# FuelGuage.net
KiCad netlist of a schematic drawn in Altium Designer
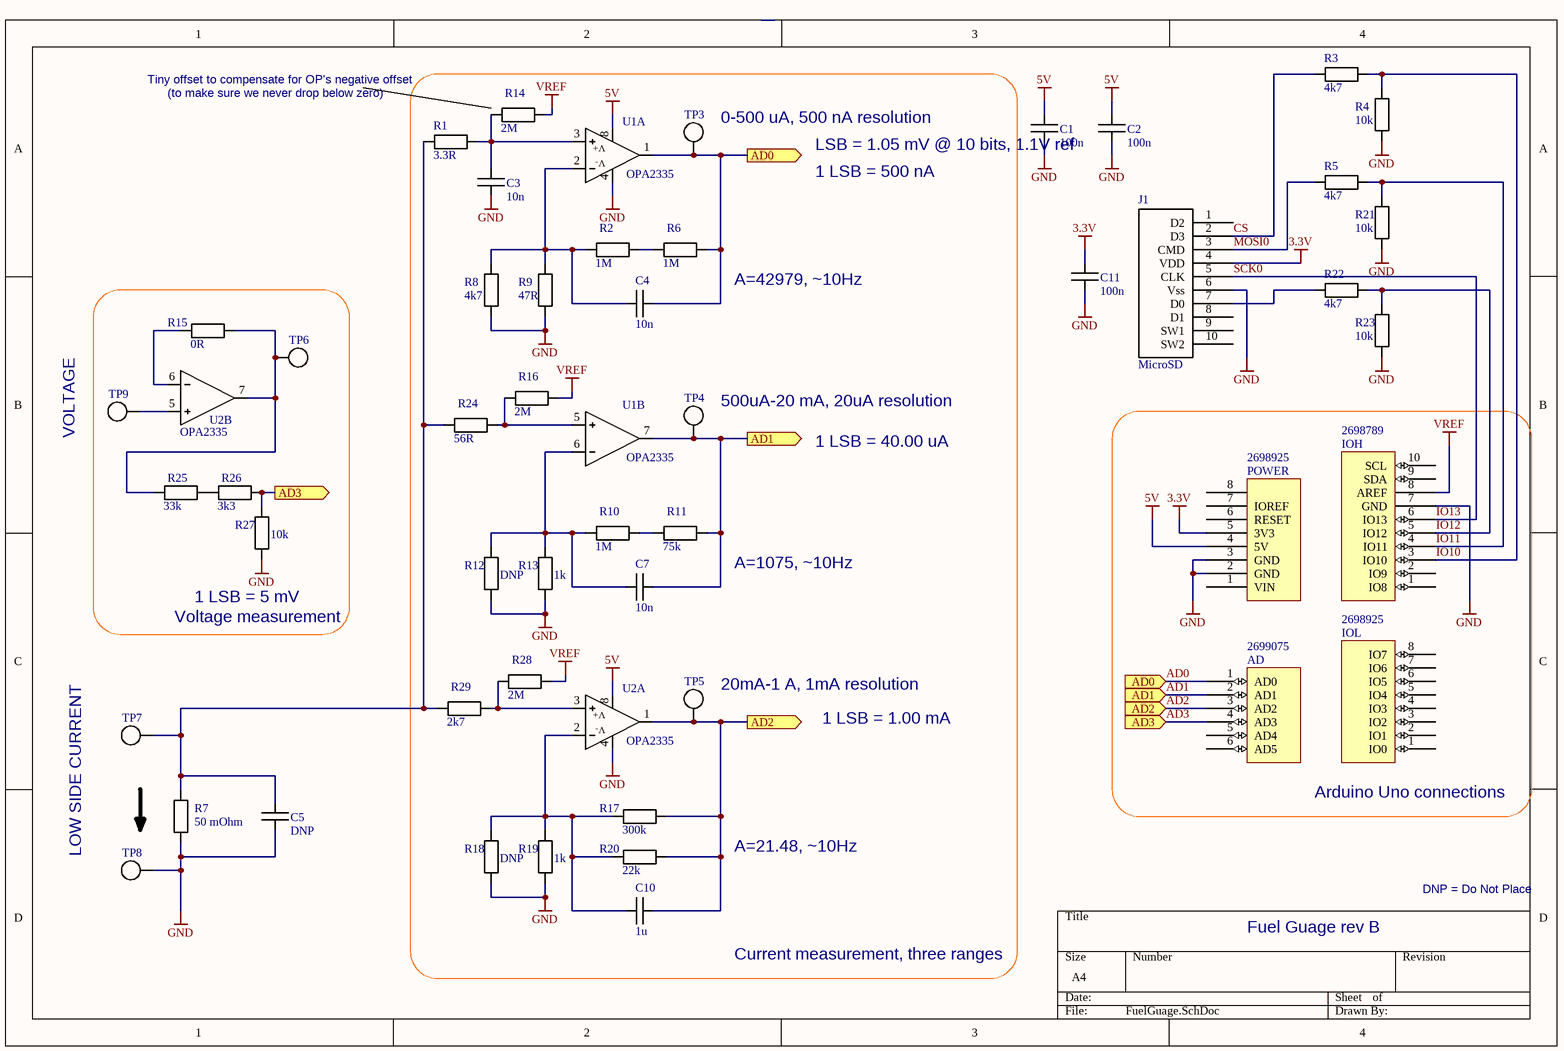
[diagram p0: FuelGuage.SchDoc]

(export (version "E")
  (design (tool "Eeschema 10.0.6"))
  (components
    (comp (ref "AD")
      (value "AD")
      (footprint "Header:Header 6x1 8.5mm")
      (fields (field (name "SUPPLIER PART NUMBER 4") "2699075"))
      (libsource (lib "Header") (part "AD"))
    )
    (comp (ref "C1")
      (value "100n")
      (footprint "0603CAP")
      (description "Ceramic Capacitor SMD 0603")
      (fields (field (name "Comment") "CAP0603"))
      (libsource (lib "PARTS") (part "185"))
    )
    (comp (ref "C2")
      (value "100n")
      (footprint "0603CAP")
      (description "Ceramic Capacitor SMD 0603")
      (fields (field (name "Comment") "CAP0603"))
      (libsource (lib "PARTS") (part "185"))
    )
    (comp (ref "C3")
      (value "10n")
      (footprint "0603CAP")
      (description "Ceramic Capacitor SMD 0603")
      (fields (field (name "Comment") "CAP0603"))
      (libsource (lib "PARTS") (part "185"))
    )
    (comp (ref "C4")
      (value "10n")
      (footprint "0603CAP")
      (description "Ceramic Capacitor SMD 0603")
      (fields (field (name "Comment") "CAP0603"))
      (libsource (lib "PARTS") (part "185"))
    )
    (comp (ref "C5")
      (value "DNP")
      (footprint "0603CAP")
      (description "Ceramic Capacitor SMD 0603")
      (fields (field (name "Comment") "CAP0603"))
      (libsource (lib "PARTS") (part "185"))
    )
    (comp (ref "C7")
      (value "10n")
      (footprint "0603CAP")
      (description "Ceramic Capacitor SMD 0603")
      (fields (field (name "Comment") "CAP0603"))
      (libsource (lib "PARTS") (part "185"))
    )
    (comp (ref "C10")
      (value "1u")
      (footprint "0603CAP")
      (description "Ceramic Capacitor SMD 0603")
      (fields (field (name "Comment") "CAP0603"))
      (libsource (lib "PARTS") (part "185"))
    )
    (comp (ref "C11")
      (value "100n")
      (footprint "0603CAP")
      (description "Ceramic Capacitor SMD 0603")
      (fields (field (name "Comment") "CAP0603"))
      (libsource (lib "PARTS") (part "185"))
    )
    (comp (ref "IOH")
      (value "IOH")
      (footprint "Header:Header 10x1 8.5mm")
      (fields (field (name "SUPPLIER PART NUMBER 3") "2698789"))
      (libsource (lib "Header") (part "IOH"))
    )
    (comp (ref "IOL")
      (value "IOL")
      (footprint "Header 8x1 8.5mm")
      (fields (field (name "SUPPLIER PART NUMBER 4") "2698925"))
      (libsource (lib "Header") (part "IOL"))
    )
    (comp (ref "J1") (value "MicroSD") (footprint "micro SD") (libsource (lib "moja") (part "MicroSD")))
    (comp (ref "POWER")
      (value "POWER_UNO")
      (footprint "Header 8x1 8.5mm")
      (fields (field (name "SUPPLIER PART NUMBER 4") "2698925"))
      (libsource (lib "Header") (part "POWER_UNO"))
    )
    (comp (ref "R1")
      (value "3.3R")
      (footprint "RES0603")
      (description "Resistor 0603 SMD")
      (fields (field (name "Comment") "RES_STANDARD"))
      (libsource (lib "PARTS") (part "276"))
    )
    (comp (ref "R2")
      (value "1M")
      (footprint "RES0603")
      (description "Resistor 0603 SMD")
      (fields (field (name "Comment") "RES_STANDARD"))
      (libsource (lib "PARTS") (part "276"))
    )
    (comp (ref "R3")
      (value "4k7")
      (footprint "RES0603")
      (description "Resistor 0603 SMD")
      (fields (field (name "Comment") "RES_STANDARD"))
      (libsource (lib "PARTS") (part "276"))
    )
    (comp (ref "R4")
      (value "10k")
      (footprint "RES0603")
      (description "Resistor 0603 SMD")
      (fields (field (name "Comment") "RES_STANDARD"))
      (libsource (lib "PARTS") (part "276"))
    )
    (comp (ref "R5")
      (value "4k7")
      (footprint "RES0603")
      (description "Resistor 0603 SMD")
      (fields (field (name "Comment") "RES_STANDARD"))
      (libsource (lib "PARTS") (part "276"))
    )
    (comp (ref "R6")
      (value "1M")
      (footprint "RES0603")
      (description "Resistor 0603 SMD")
      (fields (field (name "Comment") "RES_STANDARD"))
      (libsource (lib "PARTS") (part "276"))
    )
    (comp (ref "R7")
      (value "50 mOhm")
      (footprint "RES0603")
      (description "Resistor 0603 SMD")
      (fields (field (name "Comment") "RES_STANDARD"))
      (libsource (lib "PARTS") (part "276"))
    )
    (comp (ref "R8")
      (value "4k7")
      (footprint "RES0603")
      (description "Resistor 0603 SMD")
      (fields (field (name "Comment") "RES_STANDARD"))
      (libsource (lib "PARTS") (part "276"))
    )
    (comp (ref "R9")
      (value "47R")
      (footprint "RES0603")
      (description "Resistor 0603 SMD")
      (fields (field (name "Comment") "RES_STANDARD"))
      (libsource (lib "PARTS") (part "276"))
    )
    (comp (ref "R10")
      (value "1M")
      (footprint "RES0603")
      (description "Resistor 0603 SMD")
      (fields (field (name "Comment") "RES_STANDARD"))
      (libsource (lib "PARTS") (part "276"))
    )
    (comp (ref "R11")
      (value "75k")
      (footprint "RES0603")
      (description "Resistor 0603 SMD")
      (fields (field (name "Comment") "RES_STANDARD"))
      (libsource (lib "PARTS") (part "276"))
    )
    (comp (ref "R12")
      (value "DNP")
      (footprint "RES0603")
      (description "Resistor 0603 SMD")
      (fields (field (name "Comment") "RES_STANDARD"))
      (libsource (lib "PARTS") (part "276"))
    )
    (comp (ref "R13")
      (value "1k")
      (footprint "RES0603")
      (description "Resistor 0603 SMD")
      (fields (field (name "Comment") "RES_STANDARD"))
      (libsource (lib "PARTS") (part "276"))
    )
    (comp (ref "R14")
      (value "2M")
      (footprint "RES0603")
      (description "Resistor 0603 SMD")
      (fields (field (name "Comment") "RES_STANDARD"))
      (libsource (lib "PARTS") (part "276"))
    )
    (comp (ref "R15")
      (value "0R")
      (footprint "RES0603")
      (description "Resistor 0603 SMD")
      (fields (field (name "Comment") "RES_STANDARD"))
      (libsource (lib "PARTS") (part "276"))
    )
    (comp (ref "R16")
      (value "2M")
      (footprint "RES0603")
      (description "Resistor 0603 SMD")
      (fields (field (name "Comment") "RES_STANDARD"))
      (libsource (lib "PARTS") (part "276"))
    )
    (comp (ref "R17")
      (value "300k")
      (footprint "RES0603")
      (description "Resistor 0603 SMD")
      (fields (field (name "Comment") "RES_STANDARD"))
      (libsource (lib "PARTS") (part "276"))
    )
    (comp (ref "R18")
      (value "DNP")
      (footprint "RES0603")
      (description "Resistor 0603 SMD")
      (fields (field (name "Comment") "RES_STANDARD"))
      (libsource (lib "PARTS") (part "276"))
    )
    (comp (ref "R19")
      (value "1k")
      (footprint "RES0603")
      (description "Resistor 0603 SMD")
      (fields (field (name "Comment") "RES_STANDARD"))
      (libsource (lib "PARTS") (part "276"))
    )
    (comp (ref "R20")
      (value "22k")
      (footprint "RES0603")
      (description "Resistor 0603 SMD")
      (fields (field (name "Comment") "RES_STANDARD"))
      (libsource (lib "PARTS") (part "276"))
    )
    (comp (ref "R21")
      (value "10k")
      (footprint "RES0603")
      (description "Resistor 0603 SMD")
      (fields (field (name "Comment") "RES_STANDARD"))
      (libsource (lib "PARTS") (part "276"))
    )
    (comp (ref "R22")
      (value "4k7")
      (footprint "RES0603")
      (description "Resistor 0603 SMD")
      (fields (field (name "Comment") "RES_STANDARD"))
      (libsource (lib "PARTS") (part "276"))
    )
    (comp (ref "R23")
      (value "10k")
      (footprint "RES0603")
      (description "Resistor 0603 SMD")
      (fields (field (name "Comment") "RES_STANDARD"))
      (libsource (lib "PARTS") (part "276"))
    )
    (comp (ref "R24")
      (value "56R")
      (footprint "RES0603")
      (description "Resistor 0603 SMD")
      (fields (field (name "Comment") "RES_STANDARD"))
      (libsource (lib "PARTS") (part "276"))
    )
    (comp (ref "R25")
      (value "33k")
      (footprint "RES0603")
      (description "Resistor 0603 SMD")
      (fields (field (name "Comment") "RES_STANDARD"))
      (libsource (lib "PARTS") (part "276"))
    )
    (comp (ref "R26")
      (value "3k3")
      (footprint "RES0603")
      (description "Resistor 0603 SMD")
      (fields (field (name "Comment") "RES_STANDARD"))
      (libsource (lib "PARTS") (part "276"))
    )
    (comp (ref "R27")
      (value "10k")
      (footprint "RES0603")
      (description "Resistor 0603 SMD")
      (fields (field (name "Comment") "RES_STANDARD"))
      (libsource (lib "PARTS") (part "276"))
    )
    (comp (ref "R28")
      (value "2M")
      (footprint "RES0603")
      (description "Resistor 0603 SMD")
      (fields (field (name "Comment") "RES_STANDARD"))
      (libsource (lib "PARTS") (part "276"))
    )
    (comp (ref "R29")
      (value "2k7")
      (footprint "RES0603")
      (description "Resistor 0603 SMD")
      (fields (field (name "Comment") "RES_STANDARD"))
      (libsource (lib "PARTS") (part "276"))
    )
    (comp (ref "TP3")
      (value "TESTPOINT_1.6MM")
      (footprint "TESTPOINT_1.6MM")
      (description "Testpoint")
      (libsource (lib "PARTS") (part "203"))
    )
    (comp (ref "TP4")
      (value "TESTPOINT_1.6MM")
      (footprint "TESTPOINT_1.6MM")
      (description "Testpoint")
      (libsource (lib "PARTS") (part "203"))
    )
    (comp (ref "TP5")
      (value "TESTPOINT_1.6MM")
      (footprint "TESTPOINT_1.6MM")
      (description "Testpoint")
      (libsource (lib "PARTS") (part "203"))
    )
    (comp (ref "TP6")
      (value "TESTPOINT_1.6MM")
      (footprint "TESTPOINT_1.6MM")
      (description "Testpoint")
      (libsource (lib "PARTS") (part "203"))
    )
    (comp (ref "TP7")
      (value "TESTPOINT_1.6MM")
      (footprint "TESTPOINT_1.6MM")
      (description "Testpoint")
      (libsource (lib "PARTS") (part "203"))
    )
    (comp (ref "TP8")
      (value "TESTPOINT_1.6MM")
      (footprint "TESTPOINT_1.6MM")
      (description "Testpoint")
      (libsource (lib "PARTS") (part "203"))
    )
    (comp (ref "TP9")
      (value "TESTPOINT_1.6MM")
      (footprint "TESTPOINT_1.6MM")
      (description "Testpoint")
      (libsource (lib "PARTS") (part "203"))
    )
    (comp (ref "U1")
      (value "OPA2335")
      (footprint "SO8")
      (description "Dual and Quad 75 MHz GBW Rail-to-Rail I/O Operational")
      (libsource (lib "PARTS") (part "104"))
    )
    (comp (ref "U2")
      (value "OPA2335")
      (footprint "SO8")
      (description "Dual and Quad 75 MHz GBW Rail-to-Rail I/O Operational")
      (libsource (lib "PARTS") (part "104"))
    )
  )
  (nets
    (net (code "1") (name "/AD0") (class "Default")
      (node (ref "AD") (pin "1") (pinfunction "AD0_1") (pintype "bidirectional"))
      (node (ref "C4") (pin "2") (pinfunction "2_2") (pintype "passive"))
      (node (ref "R6") (pin "1") (pinfunction "1_1") (pintype "passive"))
      (node (ref "TP3") (pin "1") (pinfunction "1_1") (pintype "passive"))
      (node (ref "U1") (pin "1") (pinfunction "Output_A_1") (pintype "passive"))
    )
    (net (code "2") (name "/AD1") (class "Default")
      (node (ref "AD") (pin "2") (pinfunction "AD1_2") (pintype "bidirectional"))
      (node (ref "C7") (pin "2") (pinfunction "2_2") (pintype "passive"))
      (node (ref "R11") (pin "1") (pinfunction "1_1") (pintype "passive"))
      (node (ref "TP4") (pin "1") (pinfunction "1_1") (pintype "passive"))
      (node (ref "U1") (pin "7") (pinfunction "OUT_B_7") (pintype "passive"))
    )
    (net (code "3") (name "/AD2") (class "Default")
      (node (ref "AD") (pin "3") (pinfunction "AD2_3") (pintype "bidirectional"))
      (node (ref "C10") (pin "2") (pinfunction "2_2") (pintype "passive"))
      (node (ref "R17") (pin "1") (pinfunction "1_1") (pintype "passive"))
      (node (ref "R20") (pin "1") (pinfunction "1_1") (pintype "passive"))
      (node (ref "TP5") (pin "1") (pinfunction "1_1") (pintype "passive"))
      (node (ref "U2") (pin "1") (pinfunction "Output_A_1") (pintype "passive"))
    )
    (net (code "4") (name "/AD3") (class "Default")
      (node (ref "AD") (pin "4") (pinfunction "AD3_4") (pintype "bidirectional"))
      (node (ref "R26") (pin "1") (pinfunction "1_1") (pintype "passive"))
      (node (ref "R27") (pin "2") (pinfunction "2_2") (pintype "passive"))
    )
    (net (code "5") (name "/CS") (class "Default")
      (node (ref "J1") (pin "2") (pinfunction "D3_2") (pintype "passive"))
      (node (ref "R3") (pin "2") (pinfunction "2_2") (pintype "passive"))
    )
    (net (code "6") (name "/IO10") (class "Default")
      (node (ref "IOH") (pin "3") (pinfunction "IO10_3") (pintype "bidirectional"))
      (node (ref "R3") (pin "1") (pinfunction "1_1") (pintype "passive"))
      (node (ref "R4") (pin "2") (pinfunction "2_2") (pintype "passive"))
    )
    (net (code "7") (name "/IO11") (class "Default")
      (node (ref "IOH") (pin "4") (pinfunction "IO11_4") (pintype "bidirectional"))
      (node (ref "R21") (pin "2") (pinfunction "2_2") (pintype "passive"))
      (node (ref "R5") (pin "1") (pinfunction "1_1") (pintype "passive"))
    )
    (net (code "8") (name "/IO12") (class "Default")
      (node (ref "IOH") (pin "5") (pinfunction "IO12_5") (pintype "bidirectional"))
      (node (ref "R22") (pin "1") (pinfunction "1_1") (pintype "passive"))
      (node (ref "R23") (pin "2") (pinfunction "2_2") (pintype "passive"))
    )
    (net (code "9") (name "/IO13") (class "Default")
      (node (ref "IOH") (pin "6") (pinfunction "IO13_6") (pintype "bidirectional"))
      (node (ref "J1") (pin "5") (pinfunction "CLK_5") (pintype "passive"))
    )
    (net (code "10") (name "/MOSI0") (class "Default")
      (node (ref "J1") (pin "3") (pinfunction "CMD_3") (pintype "passive"))
      (node (ref "R5") (pin "2") (pinfunction "2_2") (pintype "passive"))
    )
    (net (code "11") (name "3.3V") (class "Default")
      (node (ref "C11") (pin "2") (pinfunction "2_2") (pintype "passive"))
      (node (ref "J1") (pin "4") (pinfunction "VDD_4") (pintype "passive"))
      (node (ref "POWER") (pin "5") (pinfunction "3V3_5") (pintype "power_in"))
    )
    (net (code "12") (name "5V") (class "Default")
      (node (ref "C1") (pin "2") (pinfunction "2_2") (pintype "passive"))
      (node (ref "C2") (pin "2") (pinfunction "2_2") (pintype "passive"))
      (node (ref "POWER") (pin "4") (pinfunction "5V_4") (pintype "power_in"))
      (node (ref "U1") (pin "8") (pinfunction "V+_8") (pintype "passive"))
      (node (ref "U2") (pin "8") (pinfunction "V+_8") (pintype "passive"))
    )
    (net (code "13") (name "GND") (class "Default")
      (node (ref "C1") (pin "1") (pinfunction "1_1") (pintype "passive"))
      (node (ref "C11") (pin "1") (pinfunction "1_1") (pintype "passive"))
      (node (ref "C2") (pin "1") (pinfunction "1_1") (pintype "passive"))
      (node (ref "C3") (pin "2") (pinfunction "2_2") (pintype "passive"))
      (node (ref "C5") (pin "2") (pinfunction "2_2") (pintype "passive"))
      (node (ref "IOH") (pin "7") (pinfunction "GND_7") (pintype "power_in"))
      (node (ref "J1") (pin "6") (pinfunction "Vss_6") (pintype "passive"))
      (node (ref "POWER") (pin "2") (pinfunction "GND_2") (pintype "power_in"))
      (node (ref "POWER") (pin "3") (pinfunction "GND_3") (pintype "power_in"))
      (node (ref "R12") (pin "1") (pinfunction "1_1") (pintype "passive"))
      (node (ref "R13") (pin "1") (pinfunction "1_1") (pintype "passive"))
      (node (ref "R18") (pin "1") (pinfunction "1_1") (pintype "passive"))
      (node (ref "R19") (pin "1") (pinfunction "1_1") (pintype "passive"))
      (node (ref "R21") (pin "1") (pinfunction "1_1") (pintype "passive"))
      (node (ref "R23") (pin "1") (pinfunction "1_1") (pintype "passive"))
      (node (ref "R27") (pin "1") (pinfunction "1_1") (pintype "passive"))
      (node (ref "R4") (pin "1") (pinfunction "1_1") (pintype "passive"))
      (node (ref "R7") (pin "1") (pinfunction "1_1") (pintype "passive"))
      (node (ref "R8") (pin "1") (pinfunction "1_1") (pintype "passive"))
      (node (ref "R9") (pin "1") (pinfunction "1_1") (pintype "passive"))
      (node (ref "TP8") (pin "1") (pinfunction "1_1") (pintype "passive"))
      (node (ref "U1") (pin "4") (pinfunction "V-_4") (pintype "passive"))
      (node (ref "U2") (pin "4") (pinfunction "V-_4") (pintype "passive"))
    )
    (net (code "14") (name "Net-(C5-Pad1)") (class "Default")
      (node (ref "C5") (pin "1") (pinfunction "1_1") (pintype "passive"))
      (node (ref "R1") (pin "1") (pinfunction "1_1") (pintype "passive"))
      (node (ref "R24") (pin "2") (pinfunction "2_2") (pintype "passive"))
      (node (ref "R29") (pin "2") (pinfunction "2_2") (pintype "passive"))
      (node (ref "R7") (pin "2") (pinfunction "2_2") (pintype "passive"))
      (node (ref "TP7") (pin "1") (pinfunction "1_1") (pintype "passive"))
    )
    (net (code "15") (name "Net-(J1-D0)") (class "Default")
      (node (ref "J1") (pin "7") (pinfunction "D0_7") (pintype "passive"))
      (node (ref "R22") (pin "2") (pinfunction "2_2") (pintype "passive"))
    )
    (net (code "16") (name "Net-(R2-Pad1)") (class "Default")
      (node (ref "R2") (pin "1") (pinfunction "1_1") (pintype "passive"))
      (node (ref "R6") (pin "2") (pinfunction "2_2") (pintype "passive"))
    )
    (net (code "17") (name "Net-(R10-Pad1)") (class "Default")
      (node (ref "R10") (pin "1") (pinfunction "1_1") (pintype "passive"))
      (node (ref "R11") (pin "2") (pinfunction "2_2") (pintype "passive"))
    )
    (net (code "18") (name "Net-(R25-Pad1)") (class "Default")
      (node (ref "R25") (pin "1") (pinfunction "1_1") (pintype "passive"))
      (node (ref "R26") (pin "2") (pinfunction "2_2") (pintype "passive"))
    )
    (net (code "19") (name "Net-(U1A-Inv_IN_A)") (class "Default")
      (node (ref "C4") (pin "1") (pinfunction "1_1") (pintype "passive"))
      (node (ref "R2") (pin "2") (pinfunction "2_2") (pintype "passive"))
      (node (ref "R8") (pin "2") (pinfunction "2_2") (pintype "passive"))
      (node (ref "R9") (pin "2") (pinfunction "2_2") (pintype "passive"))
      (node (ref "U1") (pin "2") (pinfunction "Inv_IN_A_2") (pintype "passive"))
    )
    (net (code "20") (name "Net-(U1A-Non-inv_IN_A)") (class "Default")
      (node (ref "C3") (pin "1") (pinfunction "1_1") (pintype "passive"))
      (node (ref "R1") (pin "2") (pinfunction "2_2") (pintype "passive"))
      (node (ref "R14") (pin "2") (pinfunction "2_2") (pintype "passive"))
      (node (ref "U1") (pin "3") (pinfunction "Non-inv_IN_A_3") (pintype "passive"))
    )
    (net (code "21") (name "Net-(U1B-Inv_IN_B)") (class "Default")
      (node (ref "C7") (pin "1") (pinfunction "1_1") (pintype "passive"))
      (node (ref "R10") (pin "2") (pinfunction "2_2") (pintype "passive"))
      (node (ref "R12") (pin "2") (pinfunction "2_2") (pintype "passive"))
      (node (ref "R13") (pin "2") (pinfunction "2_2") (pintype "passive"))
      (node (ref "U1") (pin "6") (pinfunction "Inv_IN_B_6") (pintype "passive"))
    )
    (net (code "22") (name "Net-(U1B-Non-inv_IN_B)") (class "Default")
      (node (ref "R16") (pin "2") (pinfunction "2_2") (pintype "passive"))
      (node (ref "R24") (pin "1") (pinfunction "1_1") (pintype "passive"))
      (node (ref "U1") (pin "5") (pinfunction "Non-inv_IN_B_5") (pintype "passive"))
    )
    (net (code "23") (name "Net-(U2A-Inv_IN_A)") (class "Default")
      (node (ref "C10") (pin "1") (pinfunction "1_1") (pintype "passive"))
      (node (ref "R17") (pin "2") (pinfunction "2_2") (pintype "passive"))
      (node (ref "R18") (pin "2") (pinfunction "2_2") (pintype "passive"))
      (node (ref "R19") (pin "2") (pinfunction "2_2") (pintype "passive"))
      (node (ref "R20") (pin "2") (pinfunction "2_2") (pintype "passive"))
      (node (ref "U2") (pin "2") (pinfunction "Inv_IN_A_2") (pintype "passive"))
    )
    (net (code "24") (name "Net-(U2A-Non-inv_IN_A)") (class "Default")
      (node (ref "R28") (pin "2") (pinfunction "2_2") (pintype "passive"))
      (node (ref "R29") (pin "1") (pinfunction "1_1") (pintype "passive"))
      (node (ref "U2") (pin "3") (pinfunction "Non-inv_IN_A_3") (pintype "passive"))
    )
    (net (code "25") (name "Net-(U2B-Inv_IN_B)") (class "Default")
      (node (ref "R15") (pin "2") (pinfunction "2_2") (pintype "passive"))
      (node (ref "U2") (pin "6") (pinfunction "Inv_IN_B_6") (pintype "passive"))
    )
    (net (code "26") (name "Net-(U2B-Non-inv_IN_B)") (class "Default")
      (node (ref "TP9") (pin "1") (pinfunction "1_1") (pintype "passive"))
      (node (ref "U2") (pin "5") (pinfunction "Non-inv_IN_B_5") (pintype "passive"))
    )
    (net (code "27") (name "Net-(U2B-OUT_B)") (class "Default")
      (node (ref "R15") (pin "1") (pinfunction "1_1") (pintype "passive"))
      (node (ref "R25") (pin "2") (pinfunction "2_2") (pintype "passive"))
      (node (ref "TP6") (pin "1") (pinfunction "1_1") (pintype "passive"))
      (node (ref "U2") (pin "7") (pinfunction "OUT_B_7") (pintype "passive"))
    )
    (net (code "28") (name "VREF") (class "Default")
      (node (ref "IOH") (pin "8") (pinfunction "AREF_8") (pintype "passive"))
      (node (ref "R14") (pin "1") (pinfunction "1_1") (pintype "passive"))
      (node (ref "R16") (pin "1") (pinfunction "1_1") (pintype "passive"))
      (node (ref "R28") (pin "1") (pinfunction "1_1") (pintype "passive"))
    )
    (net (code "29") (name "unconnected-(AD-AD4-Pad5)") (class "Default")
      (node (ref "AD") (pin "5") (pinfunction "AD4_5") (pintype "bidirectional"))
    )
    (net (code "30") (name "unconnected-(AD-AD5-Pad6)") (class "Default")
      (node (ref "AD") (pin "6") (pinfunction "AD5_6") (pintype "bidirectional"))
    )
    (net (code "31") (name "unconnected-(IOH-IO8-Pad1)") (class "Default")
      (node (ref "IOH") (pin "1") (pinfunction "IO8_1") (pintype "bidirectional"))
    )
    (net (code "32") (name "unconnected-(IOH-IO9-Pad2)") (class "Default")
      (node (ref "IOH") (pin "2") (pinfunction "IO9_2") (pintype "bidirectional"))
    )
    (net (code "33") (name "unconnected-(IOH-SCL-Pad10)") (class "Default")
      (node (ref "IOH") (pin "10") (pinfunction "SCL_10") (pintype "bidirectional"))
    )
    (net (code "34") (name "unconnected-(IOH-SDA-Pad9)") (class "Default")
      (node (ref "IOH") (pin "9") (pinfunction "SDA_9") (pintype "bidirectional"))
    )
    (net (code "35") (name "unconnected-(IOL-IO0-Pad1)") (class "Default")
      (node (ref "IOL") (pin "1") (pinfunction "IO0_1") (pintype "bidirectional"))
    )
    (net (code "36") (name "unconnected-(IOL-IO1-Pad2)") (class "Default")
      (node (ref "IOL") (pin "2") (pinfunction "IO1_2") (pintype "bidirectional"))
    )
    (net (code "37") (name "unconnected-(IOL-IO2-Pad3)") (class "Default")
      (node (ref "IOL") (pin "3") (pinfunction "IO2_3") (pintype "bidirectional"))
    )
    (net (code "38") (name "unconnected-(IOL-IO3-Pad4)") (class "Default")
      (node (ref "IOL") (pin "4") (pinfunction "IO3_4") (pintype "bidirectional"))
    )
    (net (code "39") (name "unconnected-(IOL-IO4-Pad5)") (class "Default")
      (node (ref "IOL") (pin "5") (pinfunction "IO4_5") (pintype "bidirectional"))
    )
    (net (code "40") (name "unconnected-(IOL-IO5-Pad6)") (class "Default")
      (node (ref "IOL") (pin "6") (pinfunction "IO5_6") (pintype "bidirectional"))
    )
    (net (code "41") (name "unconnected-(IOL-IO6-Pad7)") (class "Default")
      (node (ref "IOL") (pin "7") (pinfunction "IO6_7") (pintype "bidirectional"))
    )
    (net (code "42") (name "unconnected-(IOL-IO7-Pad8)") (class "Default")
      (node (ref "IOL") (pin "8") (pinfunction "IO7_8") (pintype "bidirectional"))
    )
    (net (code "43") (name "unconnected-(J1-D1-Pad8)") (class "Default")
      (node (ref "J1") (pin "8") (pinfunction "D1_8") (pintype "passive"))
    )
    (net (code "44") (name "unconnected-(J1-D2-Pad1)") (class "Default")
      (node (ref "J1") (pin "1") (pinfunction "D2_1") (pintype "passive"))
    )
    (net (code "45") (name "unconnected-(J1-SW1-Pad9)") (class "Default")
      (node (ref "J1") (pin "9") (pinfunction "SW1_9") (pintype "passive"))
    )
    (net (code "46") (name "unconnected-(J1-SW2-Pad10)") (class "Default")
      (node (ref "J1") (pin "10") (pinfunction "SW2_10") (pintype "passive"))
    )
    (net (code "47") (name "unconnected-(POWER-IOREF-Pad7)") (class "Default")
      (node (ref "POWER") (pin "7") (pinfunction "IOREF_7") (pintype "power_in"))
    )
    (net (code "48") (name "unconnected-(POWER-Pad8)") (class "Default")
      (node (ref "POWER") (pin "8") (pintype "passive"))
    )
    (net (code "49") (name "unconnected-(POWER-RESET-Pad6)") (class "Default")
      (node (ref "POWER") (pin "6") (pinfunction "RESET_6") (pintype "passive"))
    )
    (net (code "50") (name "unconnected-(POWER-VIN-Pad1)") (class "Default")
      (node (ref "POWER") (pin "1") (pinfunction "VIN_1") (pintype "power_in"))
    )
  )
)
